# ConstantCurrentSupply_NPN.net
KiCad netlist of a schematic drawn in EAGLE
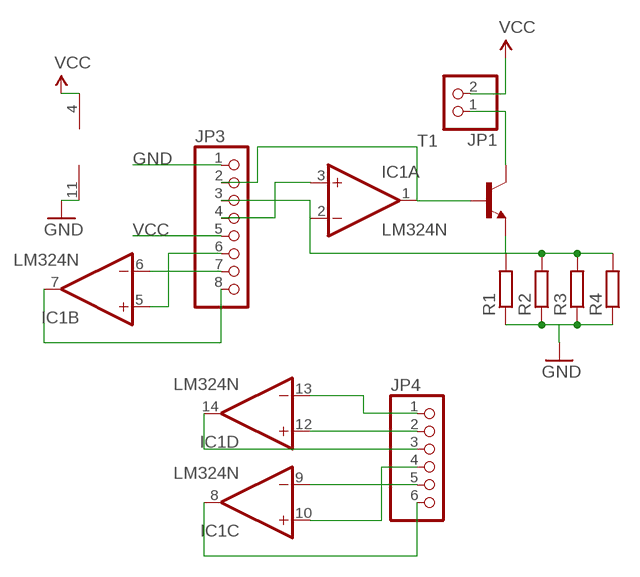
[diagram p0: schematic, sheet 1]

(export (version "E")
  (design (tool "Eeschema 10.0.6"))
  (components
    (comp (ref "IC1")
      (value "LM324N")
      (footprint "eagle-import:DIL14")
      (libsource (lib "eagle-import") (part "LM324N"))
    )
    (comp (ref "JP1")
      (value "PINHD-1X2")
      (footprint "eagle-import:1X02")
      (libsource (lib "eagle-import") (part "PINHD-1X2"))
    )
    (comp (ref "JP3")
      (value "PINHD-1X8")
      (footprint "eagle-import:1X08")
      (libsource (lib "eagle-import") (part "PINHD-1X8"))
    )
    (comp (ref "JP4")
      (value "PINHD-1X6")
      (footprint "eagle-import:1X06")
      (libsource (lib "eagle-import") (part "PINHD-1X6"))
    )
    (comp (ref "R1")
      (value "R-EU_0204/2V")
      (footprint "eagle-import:0204V")
      (libsource (lib "eagle-import") (part "R-EU_0204/2V"))
    )
    (comp (ref "R2")
      (value "R-EU_0204/2V")
      (footprint "eagle-import:0204V")
      (libsource (lib "eagle-import") (part "R-EU_0204/2V"))
    )
    (comp (ref "R3")
      (value "R-EU_0204/2V")
      (footprint "eagle-import:0204V")
      (libsource (lib "eagle-import") (part "R-EU_0204/2V"))
    )
    (comp (ref "R4")
      (value "R-EU_0204/2V")
      (footprint "eagle-import:0204V")
      (libsource (lib "eagle-import") (part "R-EU_0204/2V"))
    )
    (comp (ref "T1")
      (value "2N3904-NPN-TO92-EBC")
      (footprint "eagle-import:TO92-EBC")
      (libsource (lib "eagle-import") (part "-NPN-TO92-EBC2N3904"))
    )
  )
  (nets
    (net (code "1") (name "GND") (class "Default")
      (node (ref "IC1") (pin "11") (pinfunction "V-_11") (pintype "power_in"))
      (node (ref "JP3") (pin "1") (pinfunction "1_1") (pintype "passive"))
      (node (ref "R1") (pin "1") (pinfunction "1_1") (pintype "passive"))
      (node (ref "R2") (pin "1") (pinfunction "1_1") (pintype "passive"))
      (node (ref "R3") (pin "1") (pinfunction "1_1") (pintype "passive"))
      (node (ref "R4") (pin "1") (pinfunction "1_1") (pintype "passive"))
    )
    (net (code "2") (name "Net-(IC1A-+IN)") (class "Default")
      (node (ref "IC1") (pin "3") (pinfunction "+IN_3") (pintype "input"))
      (node (ref "JP3") (pin "4") (pinfunction "4_4") (pintype "passive"))
    )
    (net (code "3") (name "Net-(IC1A--IN)") (class "Default")
      (node (ref "IC1") (pin "2") (pinfunction "-IN_2") (pintype "input"))
      (node (ref "JP3") (pin "3") (pinfunction "3_3") (pintype "passive"))
      (node (ref "R1") (pin "2") (pinfunction "2_2") (pintype "passive"))
      (node (ref "R2") (pin "2") (pinfunction "2_2") (pintype "passive"))
      (node (ref "R3") (pin "2") (pinfunction "2_2") (pintype "passive"))
      (node (ref "R4") (pin "2") (pinfunction "2_2") (pintype "passive"))
      (node (ref "T1") (pin "E") (pinfunction "E_E") (pintype "passive"))
    )
    (net (code "4") (name "Net-(IC1A-OUT)") (class "Default")
      (node (ref "IC1") (pin "1") (pinfunction "OUT_1") (pintype "output"))
      (node (ref "JP3") (pin "2") (pinfunction "2_2") (pintype "passive"))
      (node (ref "T1") (pin "B") (pinfunction "B_B") (pintype "passive"))
    )
    (net (code "5") (name "Net-(IC1B-+IN)") (class "Default")
      (node (ref "IC1") (pin "5") (pinfunction "+IN_5") (pintype "input"))
      (node (ref "JP3") (pin "6") (pinfunction "6_6") (pintype "passive"))
    )
    (net (code "6") (name "Net-(IC1B--IN)") (class "Default")
      (node (ref "IC1") (pin "6") (pinfunction "-IN_6") (pintype "input"))
      (node (ref "JP3") (pin "7") (pinfunction "7_7") (pintype "passive"))
    )
    (net (code "7") (name "Net-(IC1B-OUT)") (class "Default")
      (node (ref "IC1") (pin "7") (pinfunction "OUT_7") (pintype "output"))
      (node (ref "JP3") (pin "8") (pinfunction "8_8") (pintype "passive"))
    )
    (net (code "8") (name "Net-(IC1C-+IN)") (class "Default")
      (node (ref "IC1") (pin "10") (pinfunction "+IN_10") (pintype "input"))
      (node (ref "JP4") (pin "4") (pinfunction "4_4") (pintype "passive"))
    )
    (net (code "9") (name "Net-(IC1C--IN)") (class "Default")
      (node (ref "IC1") (pin "9") (pinfunction "-IN_9") (pintype "input"))
      (node (ref "JP4") (pin "5") (pinfunction "5_5") (pintype "passive"))
    )
    (net (code "10") (name "Net-(IC1C-OUT)") (class "Default")
      (node (ref "IC1") (pin "8") (pinfunction "OUT_8") (pintype "output"))
      (node (ref "JP4") (pin "6") (pinfunction "6_6") (pintype "passive"))
    )
    (net (code "11") (name "Net-(IC1D-+IN)") (class "Default")
      (node (ref "IC1") (pin "12") (pinfunction "+IN_12") (pintype "input"))
      (node (ref "JP4") (pin "2") (pinfunction "2_2") (pintype "passive"))
    )
    (net (code "12") (name "Net-(IC1D--IN)") (class "Default")
      (node (ref "IC1") (pin "13") (pinfunction "-IN_13") (pintype "input"))
      (node (ref "JP4") (pin "1") (pinfunction "1_1") (pintype "passive"))
    )
    (net (code "13") (name "Net-(IC1D-OUT)") (class "Default")
      (node (ref "IC1") (pin "14") (pinfunction "OUT_14") (pintype "output"))
      (node (ref "JP4") (pin "3") (pinfunction "3_3") (pintype "passive"))
    )
    (net (code "14") (name "Net-(JP1-Pad1)") (class "Default")
      (node (ref "JP1") (pin "1") (pinfunction "1_1") (pintype "passive"))
      (node (ref "T1") (pin "C") (pinfunction "C_C") (pintype "passive"))
    )
    (net (code "15") (name "VCC") (class "Default")
      (node (ref "IC1") (pin "4") (pinfunction "V+_4") (pintype "power_in"))
      (node (ref "JP1") (pin "2") (pinfunction "2_2") (pintype "passive"))
      (node (ref "JP3") (pin "5") (pinfunction "5_5") (pintype "passive"))
    )
  )
)
